# DC-DC_TPS54627DDAR.net
KiCad netlist of a schematic drawn in Altium Designer
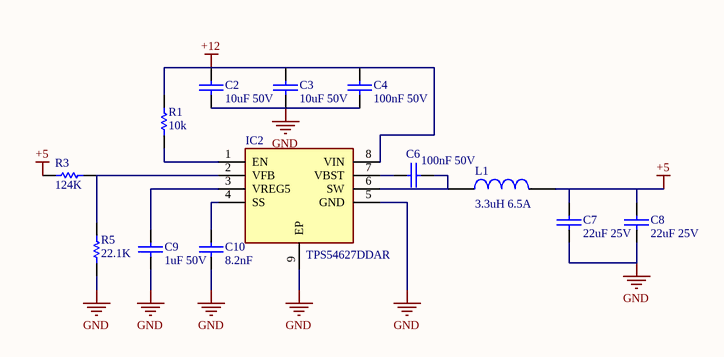
[diagram p0: DC-DC TPS54627DDAR.SchDoc]

(export (version "E")
  (design (tool "Eeschema 10.0.6"))
  (components
    (comp (ref "C2") (value "10uF 50V") (footprint "1206C") (libsource (lib "电容") (part "CAP-NP")))
    (comp (ref "C3") (value "10uF 50V") (footprint "1206C") (libsource (lib "电容") (part "CAP-NP")))
    (comp (ref "C4") (value "100nF 50V") (footprint "0603C") (libsource (lib "电容") (part "CAP-NP")))
    (comp (ref "C6") (value "100nF 50V") (footprint "电容:0603C") (libsource (lib "电容") (part "CAP-NP")))
    (comp (ref "C7") (value "22uF 25V") (footprint "电容:0805C") (libsource (lib "电容") (part "CAP-NP")))
    (comp (ref "C8") (value "22uF 25V") (footprint "电容:0805C") (libsource (lib "电容") (part "CAP-NP")))
    (comp (ref "C9") (value "1uF 50V") (footprint "电容:0603C") (libsource (lib "电容") (part "CAP-NP")))
    (comp (ref "C10") (value "8.2nF") (footprint "电容:0603C") (libsource (lib "电容") (part "CAP-NP")))
    (comp (ref "IC2")
      (value "TPS54627DDAR")
      (footprint "SamacSys:SOIC127P600X170-9N")
      (description "Integrated Circuit")
      (fields (field (name "MOUSER PART NUMBER") "595-TPS54627DDAR"))
      (libsource (lib "*") (part "TPS54627DDAR"))
    )
    (comp (ref "L1")
      (value "3.3uH 6.5A")
      (footprint "Inductance:SMD 7.3x6.6")
      (description "MHCI06030-3R3M-R8A")
      (libsource (lib "电感") (part "INDUCTOR"))
    )
    (comp (ref "R1") (value "10k") (footprint "0402R") (libsource (lib "Resistor") (part "RES")))
    (comp (ref "R3") (value "124K") (footprint "0402R") (libsource (lib "Resistor") (part "RES")))
    (comp (ref "R5") (value "22.1K") (footprint "0402R") (libsource (lib "Resistor") (part "RES")))
  )
  (nets
    (net (code "1") (name "+5") (class "Default")
      (node (ref "C7") (pin "2") (pinfunction "2_2") (pintype "passive"))
      (node (ref "C8") (pin "2") (pinfunction "2_2") (pintype "passive"))
      (node (ref "L1") (pin "2") (pinfunction "2_2") (pintype "passive"))
      (node (ref "R3") (pin "1") (pinfunction "1_1") (pintype "passive"))
    )
    (net (code "2") (name "+12") (class "Default")
      (node (ref "C2") (pin "2") (pinfunction "2_2") (pintype "passive"))
      (node (ref "C3") (pin "2") (pinfunction "2_2") (pintype "passive"))
      (node (ref "C4") (pin "2") (pinfunction "2_2") (pintype "passive"))
      (node (ref "IC2") (pin "8") (pinfunction "VIN_8") (pintype "passive"))
      (node (ref "R1") (pin "2") (pinfunction "2_2") (pintype "passive"))
    )
    (net (code "3") (name "GND") (class "Default")
      (node (ref "C10") (pin "1") (pinfunction "1_1") (pintype "passive"))
      (node (ref "C2") (pin "1") (pinfunction "1_1") (pintype "passive"))
      (node (ref "C3") (pin "1") (pinfunction "1_1") (pintype "passive"))
      (node (ref "C4") (pin "1") (pinfunction "1_1") (pintype "passive"))
      (node (ref "C7") (pin "1") (pinfunction "1_1") (pintype "passive"))
      (node (ref "C8") (pin "1") (pinfunction "1_1") (pintype "passive"))
      (node (ref "C9") (pin "2") (pinfunction "2_2") (pintype "passive"))
      (node (ref "IC2") (pin "5") (pinfunction "GND_5") (pintype "passive"))
      (node (ref "IC2") (pin "9") (pinfunction "EP_9") (pintype "passive"))
      (node (ref "R5") (pin "1") (pinfunction "1_1") (pintype "passive"))
    )
    (net (code "4") (name "Net-(IC2-EN)") (class "Default")
      (node (ref "IC2") (pin "1") (pinfunction "EN_1") (pintype "passive"))
      (node (ref "R1") (pin "1") (pinfunction "1_1") (pintype "passive"))
    )
    (net (code "5") (name "Net-(IC2-SS)") (class "Default")
      (node (ref "C10") (pin "2") (pinfunction "2_2") (pintype "passive"))
      (node (ref "IC2") (pin "4") (pinfunction "SS_4") (pintype "passive"))
    )
    (net (code "6") (name "Net-(IC2-SW)") (class "Default")
      (node (ref "C6") (pin "1") (pinfunction "1_1") (pintype "passive"))
      (node (ref "IC2") (pin "6") (pinfunction "SW_6") (pintype "passive"))
      (node (ref "L1") (pin "1") (pinfunction "1_1") (pintype "passive"))
    )
    (net (code "7") (name "Net-(IC2-VBST)") (class "Default")
      (node (ref "C6") (pin "2") (pinfunction "2_2") (pintype "passive"))
      (node (ref "IC2") (pin "7") (pinfunction "VBST_7") (pintype "passive"))
    )
    (net (code "8") (name "Net-(IC2-VFB)") (class "Default")
      (node (ref "IC2") (pin "2") (pinfunction "VFB_2") (pintype "passive"))
      (node (ref "R3") (pin "2") (pinfunction "2_2") (pintype "passive"))
      (node (ref "R5") (pin "2") (pinfunction "2_2") (pintype "passive"))
    )
    (net (code "9") (name "Net-(IC2-VREG5)") (class "Default")
      (node (ref "C9") (pin "1") (pinfunction "1_1") (pintype "passive"))
      (node (ref "IC2") (pin "3") (pinfunction "VREG5_3") (pintype "passive"))
    )
  )
)
